# ProPrj_Space_Weight_2026-05-02.net
KiCad netlist of a schematic drawn in EasyEDA Pro
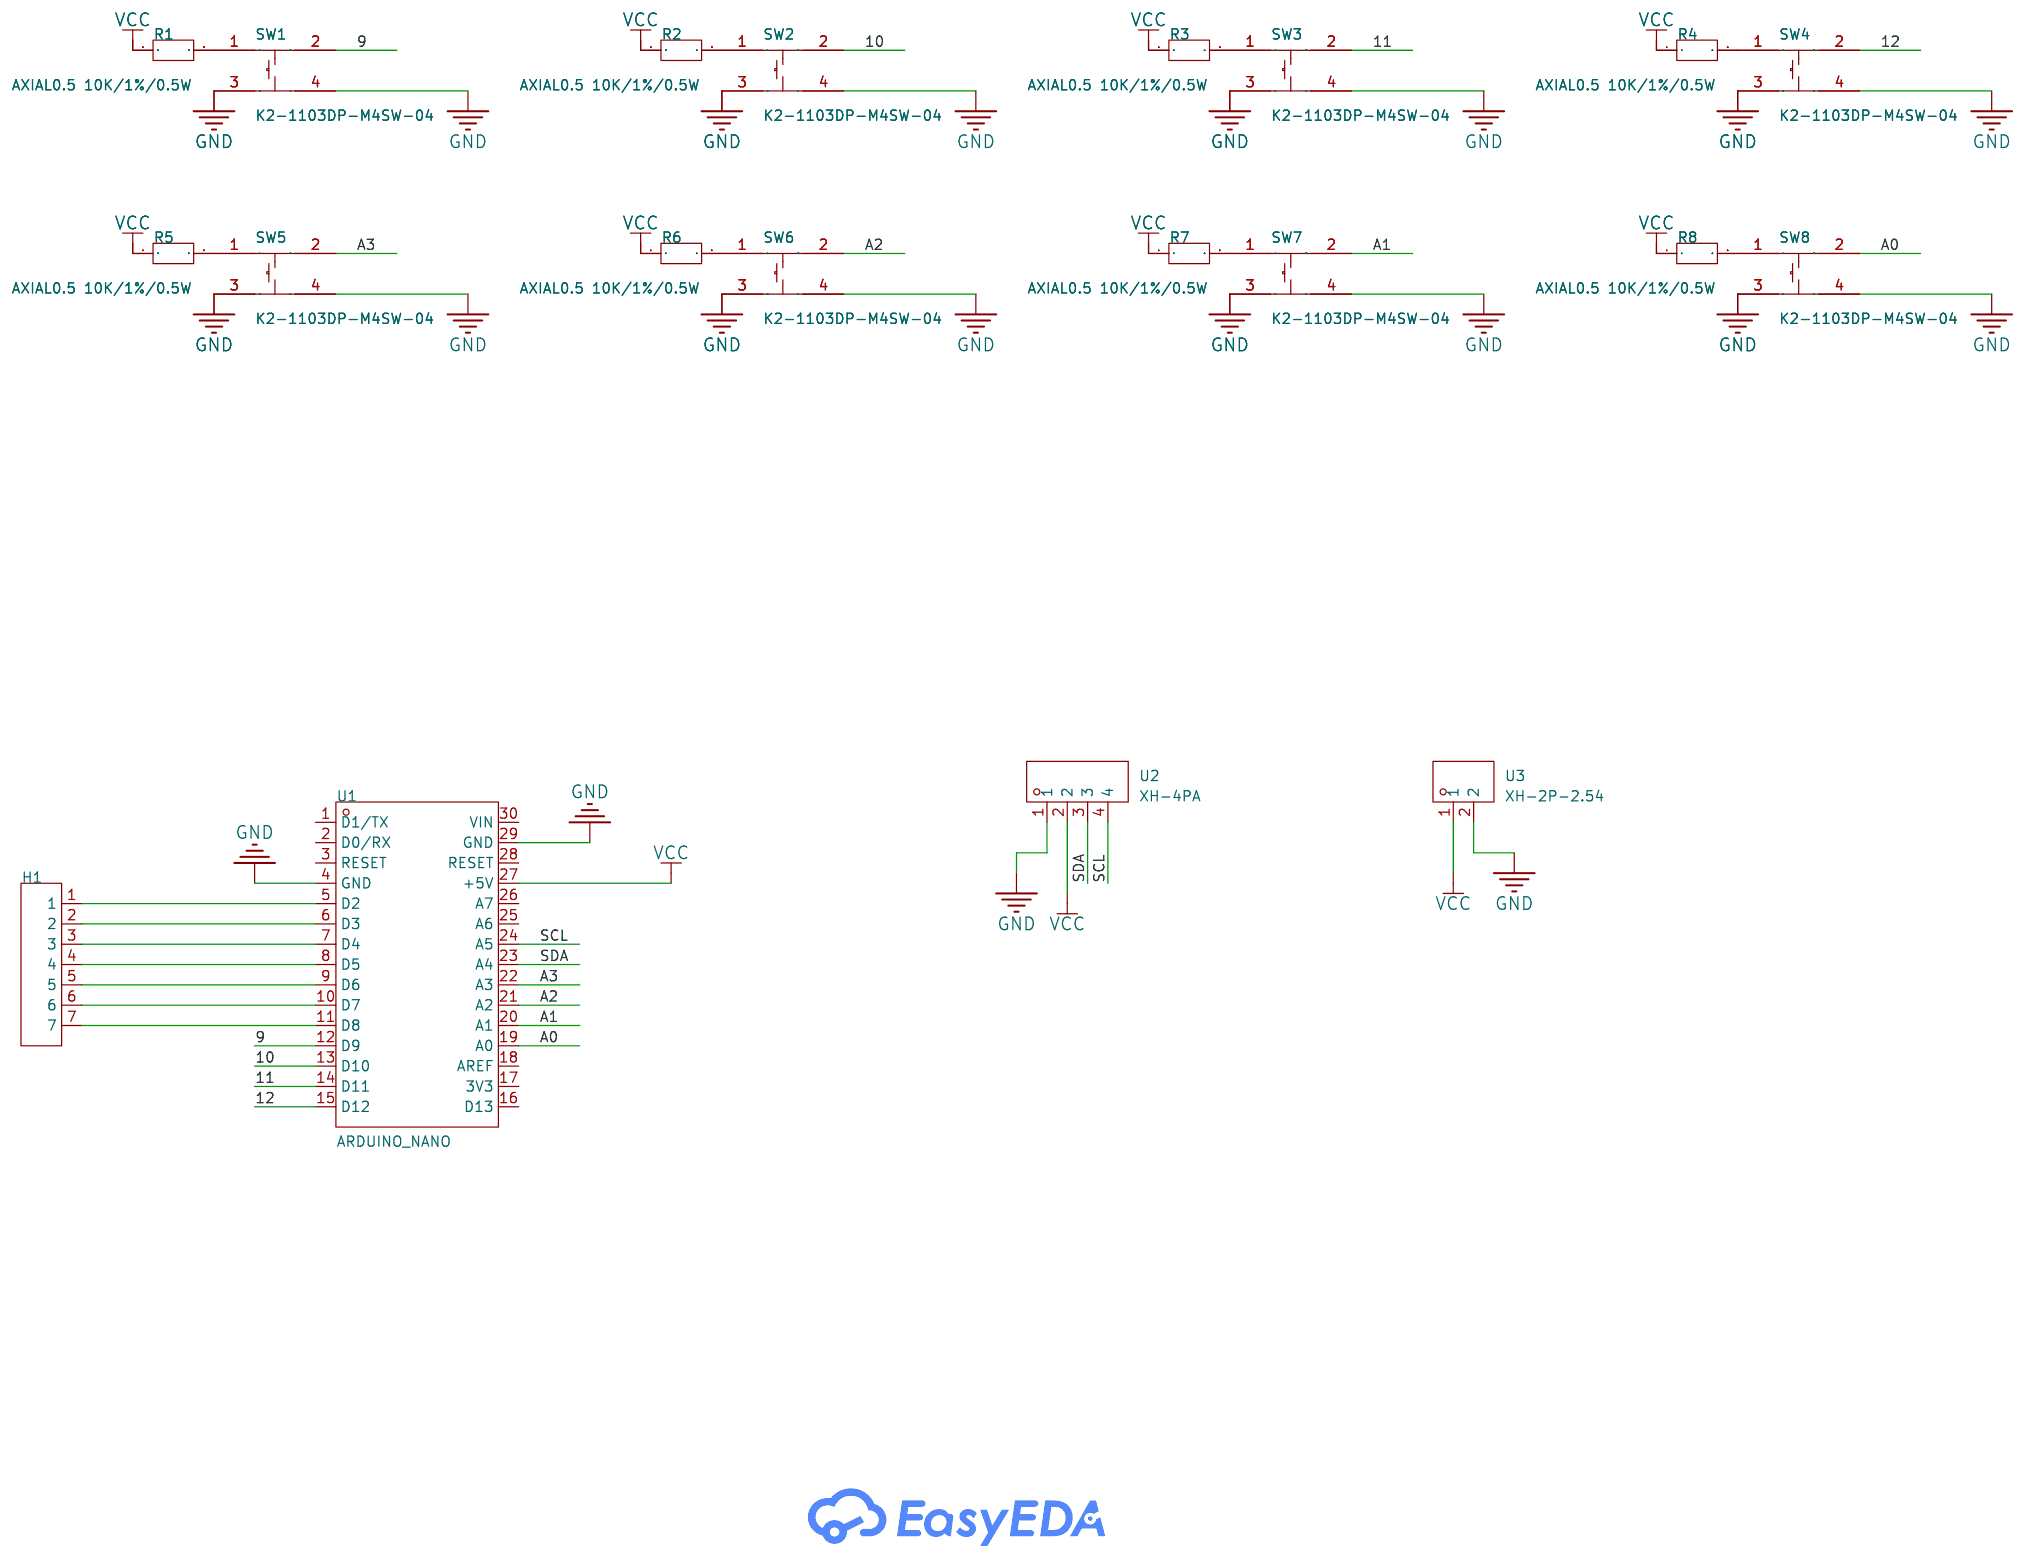
[diagram p0: schematic sheet]

(export (version "E")
  (design (tool "Eeschema 10.0.6"))
  (components
    (comp (ref "H1")
      (value "~")
      (footprint "easyedapro:HDR-TH_7P-P2.54-V-M")
      (libsource (lib "easyedapro") (part "PZ254V-11-07P"))
    )
    (comp (ref "R1")
      (value "AXIAL0.5 10K/1%/0.5W")
      (footprint "easyedapro:RES-TH_BD3.0-L9.0-P13.0-D0.6")
      (libsource (lib "easyedapro") (part "AXIAL0.5 10K/1%/0.5W"))
    )
    (comp (ref "R2")
      (value "AXIAL0.5 10K/1%/0.5W")
      (footprint "easyedapro:RES-TH_BD3.0-L9.0-P13.0-D0.6")
      (libsource (lib "easyedapro") (part "AXIAL0.5 10K/1%/0.5W"))
    )
    (comp (ref "R3")
      (value "AXIAL0.5 10K/1%/0.5W")
      (footprint "easyedapro:RES-TH_BD3.0-L9.0-P13.0-D0.6")
      (libsource (lib "easyedapro") (part "AXIAL0.5 10K/1%/0.5W"))
    )
    (comp (ref "R4")
      (value "AXIAL0.5 10K/1%/0.5W")
      (footprint "easyedapro:RES-TH_BD3.0-L9.0-P13.0-D0.6")
      (libsource (lib "easyedapro") (part "AXIAL0.5 10K/1%/0.5W"))
    )
    (comp (ref "R5")
      (value "AXIAL0.5 10K/1%/0.5W")
      (footprint "easyedapro:RES-TH_BD3.0-L9.0-P13.0-D0.6")
      (libsource (lib "easyedapro") (part "AXIAL0.5 10K/1%/0.5W"))
    )
    (comp (ref "R6")
      (value "AXIAL0.5 10K/1%/0.5W")
      (footprint "easyedapro:RES-TH_BD3.0-L9.0-P13.0-D0.6")
      (libsource (lib "easyedapro") (part "AXIAL0.5 10K/1%/0.5W"))
    )
    (comp (ref "R7")
      (value "AXIAL0.5 10K/1%/0.5W")
      (footprint "easyedapro:RES-TH_BD3.0-L9.0-P13.0-D0.6")
      (libsource (lib "easyedapro") (part "AXIAL0.5 10K/1%/0.5W"))
    )
    (comp (ref "R8")
      (value "AXIAL0.5 10K/1%/0.5W")
      (footprint "easyedapro:RES-TH_BD3.0-L9.0-P13.0-D0.6")
      (libsource (lib "easyedapro") (part "AXIAL0.5 10K/1%/0.5W"))
    )
    (comp (ref "SW1")
      (value "K2-1103DP-M4SW-04")
      (footprint "easyedapro:SW-TH_4P-L12.0-W12.0-P5.00-LS12.5_TC-1103XX")
      (libsource (lib "easyedapro") (part "K2-1103DP-M4SW-04"))
    )
    (comp (ref "SW2")
      (value "K2-1103DP-M4SW-04")
      (footprint "easyedapro:SW-TH_4P-L12.0-W12.0-P5.00-LS12.5_TC-1103XX")
      (libsource (lib "easyedapro") (part "K2-1103DP-M4SW-04"))
    )
    (comp (ref "SW3")
      (value "K2-1103DP-M4SW-04")
      (footprint "easyedapro:SW-TH_4P-L12.0-W12.0-P5.00-LS12.5_TC-1103XX")
      (libsource (lib "easyedapro") (part "K2-1103DP-M4SW-04"))
    )
    (comp (ref "SW4")
      (value "K2-1103DP-M4SW-04")
      (footprint "easyedapro:SW-TH_4P-L12.0-W12.0-P5.00-LS12.5_TC-1103XX")
      (libsource (lib "easyedapro") (part "K2-1103DP-M4SW-04"))
    )
    (comp (ref "SW5")
      (value "K2-1103DP-M4SW-04")
      (footprint "easyedapro:SW-TH_4P-L12.0-W12.0-P5.00-LS12.5_TC-1103XX")
      (libsource (lib "easyedapro") (part "K2-1103DP-M4SW-04"))
    )
    (comp (ref "SW6")
      (value "K2-1103DP-M4SW-04")
      (footprint "easyedapro:SW-TH_4P-L12.0-W12.0-P5.00-LS12.5_TC-1103XX")
      (libsource (lib "easyedapro") (part "K2-1103DP-M4SW-04"))
    )
    (comp (ref "SW7")
      (value "K2-1103DP-M4SW-04")
      (footprint "easyedapro:SW-TH_4P-L12.0-W12.0-P5.00-LS12.5_TC-1103XX")
      (libsource (lib "easyedapro") (part "K2-1103DP-M4SW-04"))
    )
    (comp (ref "SW8")
      (value "K2-1103DP-M4SW-04")
      (footprint "easyedapro:SW-TH_4P-L12.0-W12.0-P5.00-LS12.5_TC-1103XX")
      (libsource (lib "easyedapro") (part "K2-1103DP-M4SW-04"))
    )
    (comp (ref "U1")
      (value "ARDUINO_NANO")
      (footprint "easyedapro:COMM-TH_ARDUINO_NANO")
      (libsource (lib "easyedapro") (part "ARDUINO_NANO"))
    )
    (comp (ref "U2")
      (value "XH-4PA")
      (footprint "easyedapro:CONN-TH_4P-P2.50_ZHOURI_XH-4PA")
      (fields (field (name "Manufacturer") "ZHOURI(洲日)"))
      (libsource (lib "easyedapro") (part "XH-4PA"))
    )
    (comp (ref "U3")
      (value "XH-2P-2.54")
      (footprint "easyedapro:CONN-TH_2P-P2.50-XH2.54-2P")
      (libsource (lib "easyedapro") (part "XH-2P-2.54"))
    )
  )
  (nets
    (net (code "1") (name "/9") (class "Default")
      (node (ref "SW1") (pin "2") (pinfunction "2_2") (pintype "unspecified"))
      (node (ref "U1") (pin "12") (pinfunction "D9_12") (pintype "unspecified"))
    )
    (net (code "2") (name "/10") (class "Default")
      (node (ref "SW2") (pin "2") (pinfunction "2_2") (pintype "unspecified"))
      (node (ref "U1") (pin "13") (pinfunction "D10_13") (pintype "unspecified"))
    )
    (net (code "3") (name "/11") (class "Default")
      (node (ref "SW3") (pin "2") (pinfunction "2_2") (pintype "unspecified"))
      (node (ref "U1") (pin "14") (pinfunction "D11_14") (pintype "unspecified"))
    )
    (net (code "4") (name "/12") (class "Default")
      (node (ref "SW4") (pin "2") (pinfunction "2_2") (pintype "unspecified"))
      (node (ref "U1") (pin "15") (pinfunction "D12_15") (pintype "unspecified"))
    )
    (net (code "5") (name "/A0") (class "Default")
      (node (ref "SW8") (pin "2") (pinfunction "2_2") (pintype "unspecified"))
      (node (ref "U1") (pin "19") (pinfunction "A0_19") (pintype "unspecified"))
    )
    (net (code "6") (name "/A1") (class "Default")
      (node (ref "SW7") (pin "2") (pinfunction "2_2") (pintype "unspecified"))
      (node (ref "U1") (pin "20") (pinfunction "A1_20") (pintype "unspecified"))
    )
    (net (code "7") (name "/A2") (class "Default")
      (node (ref "SW6") (pin "2") (pinfunction "2_2") (pintype "unspecified"))
      (node (ref "U1") (pin "21") (pinfunction "A2_21") (pintype "unspecified"))
    )
    (net (code "8") (name "/A3") (class "Default")
      (node (ref "SW5") (pin "2") (pinfunction "2_2") (pintype "unspecified"))
      (node (ref "U1") (pin "22") (pinfunction "A3_22") (pintype "unspecified"))
    )
    (net (code "9") (name "/SCL") (class "Default")
      (node (ref "U1") (pin "24") (pinfunction "A5_24") (pintype "unspecified"))
      (node (ref "U2") (pin "4") (pinfunction "4_4") (pintype "input"))
    )
    (net (code "10") (name "/SDA") (class "Default")
      (node (ref "U1") (pin "23") (pinfunction "A4_23") (pintype "unspecified"))
      (node (ref "U2") (pin "3") (pinfunction "3_3") (pintype "input"))
    )
    (net (code "11") (name "GND") (class "Default")
      (node (ref "SW1") (pin "3") (pinfunction "3_3") (pintype "unspecified"))
      (node (ref "SW1") (pin "4") (pinfunction "4_4") (pintype "unspecified"))
      (node (ref "SW2") (pin "3") (pinfunction "3_3") (pintype "unspecified"))
      (node (ref "SW2") (pin "4") (pinfunction "4_4") (pintype "unspecified"))
      (node (ref "SW3") (pin "3") (pinfunction "3_3") (pintype "unspecified"))
      (node (ref "SW3") (pin "4") (pinfunction "4_4") (pintype "unspecified"))
      (node (ref "SW4") (pin "3") (pinfunction "3_3") (pintype "unspecified"))
      (node (ref "SW4") (pin "4") (pinfunction "4_4") (pintype "unspecified"))
      (node (ref "SW5") (pin "3") (pinfunction "3_3") (pintype "unspecified"))
      (node (ref "SW5") (pin "4") (pinfunction "4_4") (pintype "unspecified"))
      (node (ref "SW6") (pin "3") (pinfunction "3_3") (pintype "unspecified"))
      (node (ref "SW6") (pin "4") (pinfunction "4_4") (pintype "unspecified"))
      (node (ref "SW7") (pin "3") (pinfunction "3_3") (pintype "unspecified"))
      (node (ref "SW7") (pin "4") (pinfunction "4_4") (pintype "unspecified"))
      (node (ref "SW8") (pin "3") (pinfunction "3_3") (pintype "unspecified"))
      (node (ref "SW8") (pin "4") (pinfunction "4_4") (pintype "unspecified"))
      (node (ref "U1") (pin "29") (pinfunction "GND_29") (pintype "unspecified"))
      (node (ref "U1") (pin "4") (pinfunction "GND_4") (pintype "unspecified"))
      (node (ref "U2") (pin "1") (pinfunction "1_1") (pintype "input"))
      (node (ref "U3") (pin "2") (pinfunction "2_2") (pintype "unspecified"))
    )
    (net (code "12") (name "Net-(R1-Pad2)") (class "Default")
      (node (ref "R1") (pin "2") (pinfunction "2_2") (pintype "unspecified"))
      (node (ref "SW1") (pin "1") (pinfunction "1_1") (pintype "unspecified"))
    )
    (net (code "13") (name "Net-(R2-Pad2)") (class "Default")
      (node (ref "R2") (pin "2") (pinfunction "2_2") (pintype "unspecified"))
      (node (ref "SW2") (pin "1") (pinfunction "1_1") (pintype "unspecified"))
    )
    (net (code "14") (name "Net-(R3-Pad2)") (class "Default")
      (node (ref "R3") (pin "2") (pinfunction "2_2") (pintype "unspecified"))
      (node (ref "SW3") (pin "1") (pinfunction "1_1") (pintype "unspecified"))
    )
    (net (code "15") (name "Net-(R4-Pad2)") (class "Default")
      (node (ref "R4") (pin "2") (pinfunction "2_2") (pintype "unspecified"))
      (node (ref "SW4") (pin "1") (pinfunction "1_1") (pintype "unspecified"))
    )
    (net (code "16") (name "Net-(R5-Pad2)") (class "Default")
      (node (ref "R5") (pin "2") (pinfunction "2_2") (pintype "unspecified"))
      (node (ref "SW5") (pin "1") (pinfunction "1_1") (pintype "unspecified"))
    )
    (net (code "17") (name "Net-(R6-Pad2)") (class "Default")
      (node (ref "R6") (pin "2") (pinfunction "2_2") (pintype "unspecified"))
      (node (ref "SW6") (pin "1") (pinfunction "1_1") (pintype "unspecified"))
    )
    (net (code "18") (name "Net-(R7-Pad2)") (class "Default")
      (node (ref "R7") (pin "2") (pinfunction "2_2") (pintype "unspecified"))
      (node (ref "SW7") (pin "1") (pinfunction "1_1") (pintype "unspecified"))
    )
    (net (code "19") (name "Net-(R8-Pad2)") (class "Default")
      (node (ref "R8") (pin "2") (pinfunction "2_2") (pintype "unspecified"))
      (node (ref "SW8") (pin "1") (pinfunction "1_1") (pintype "unspecified"))
    )
    (net (code "20") (name "Net-(U1-D2)") (class "Default")
      (node (ref "H1") (pin "1") (pinfunction "1_1") (pintype "unspecified"))
      (node (ref "U1") (pin "5") (pinfunction "D2_5") (pintype "unspecified"))
    )
    (net (code "21") (name "Net-(U1-D3)") (class "Default")
      (node (ref "H1") (pin "2") (pinfunction "2_2") (pintype "unspecified"))
      (node (ref "U1") (pin "6") (pinfunction "D3_6") (pintype "unspecified"))
    )
    (net (code "22") (name "Net-(U1-D4)") (class "Default")
      (node (ref "H1") (pin "3") (pinfunction "3_3") (pintype "unspecified"))
      (node (ref "U1") (pin "7") (pinfunction "D4_7") (pintype "unspecified"))
    )
    (net (code "23") (name "Net-(U1-D5)") (class "Default")
      (node (ref "H1") (pin "4") (pinfunction "4_4") (pintype "unspecified"))
      (node (ref "U1") (pin "8") (pinfunction "D5_8") (pintype "unspecified"))
    )
    (net (code "24") (name "Net-(U1-D6)") (class "Default")
      (node (ref "H1") (pin "5") (pinfunction "5_5") (pintype "unspecified"))
      (node (ref "U1") (pin "9") (pinfunction "D6_9") (pintype "unspecified"))
    )
    (net (code "25") (name "Net-(U1-D7)") (class "Default")
      (node (ref "H1") (pin "6") (pinfunction "6_6") (pintype "unspecified"))
      (node (ref "U1") (pin "10") (pinfunction "D7_10") (pintype "unspecified"))
    )
    (net (code "26") (name "Net-(U1-D8)") (class "Default")
      (node (ref "H1") (pin "7") (pinfunction "7_7") (pintype "unspecified"))
      (node (ref "U1") (pin "11") (pinfunction "D8_11") (pintype "unspecified"))
    )
    (net (code "27") (name "VCC") (class "Default")
      (node (ref "R1") (pin "1") (pinfunction "1_1") (pintype "unspecified"))
      (node (ref "R2") (pin "1") (pinfunction "1_1") (pintype "unspecified"))
      (node (ref "R3") (pin "1") (pinfunction "1_1") (pintype "unspecified"))
      (node (ref "R4") (pin "1") (pinfunction "1_1") (pintype "unspecified"))
      (node (ref "R5") (pin "1") (pinfunction "1_1") (pintype "unspecified"))
      (node (ref "R6") (pin "1") (pinfunction "1_1") (pintype "unspecified"))
      (node (ref "R7") (pin "1") (pinfunction "1_1") (pintype "unspecified"))
      (node (ref "R8") (pin "1") (pinfunction "1_1") (pintype "unspecified"))
      (node (ref "U1") (pin "27") (pinfunction "+5V_27") (pintype "unspecified"))
      (node (ref "U2") (pin "2") (pinfunction "2_2") (pintype "input"))
      (node (ref "U3") (pin "1") (pinfunction "1_1") (pintype "unspecified"))
    )
    (net (code "28") (name "unconnected-(U1-3V3-Pad17)") (class "Default")
      (node (ref "U1") (pin "17") (pinfunction "3V3_17") (pintype "unspecified"))
    )
    (net (code "29") (name "unconnected-(U1-A6-Pad25)") (class "Default")
      (node (ref "U1") (pin "25") (pinfunction "A6_25") (pintype "unspecified"))
    )
    (net (code "30") (name "unconnected-(U1-A7-Pad26)") (class "Default")
      (node (ref "U1") (pin "26") (pinfunction "A7_26") (pintype "unspecified"))
    )
    (net (code "31") (name "unconnected-(U1-AREF-Pad18)") (class "Default")
      (node (ref "U1") (pin "18") (pinfunction "AREF_18") (pintype "unspecified"))
    )
    (net (code "32") (name "unconnected-(U1-D0{slash}RX-Pad2)") (class "Default")
      (node (ref "U1") (pin "2") (pinfunction "D0/RX_2") (pintype "unspecified"))
    )
    (net (code "33") (name "unconnected-(U1-D1{slash}TX-Pad1)") (class "Default")
      (node (ref "U1") (pin "1") (pinfunction "D1/TX_1") (pintype "unspecified"))
    )
    (net (code "34") (name "unconnected-(U1-D13-Pad16)") (class "Default")
      (node (ref "U1") (pin "16") (pinfunction "D13_16") (pintype "unspecified"))
    )
    (net (code "35") (name "unconnected-(U1-RESET-Pad3)") (class "Default")
      (node (ref "U1") (pin "3") (pinfunction "RESET_3") (pintype "unspecified"))
    )
    (net (code "36") (name "unconnected-(U1-RESET-Pad28)") (class "Default")
      (node (ref "U1") (pin "28") (pinfunction "RESET_28") (pintype "unspecified"))
    )
    (net (code "37") (name "unconnected-(U1-VIN-Pad30)") (class "Default")
      (node (ref "U1") (pin "30") (pinfunction "VIN_30") (pintype "unspecified"))
    )
  )
)
